# Steering_PCB.net
KiCad netlist of a schematic drawn in Altium Designer
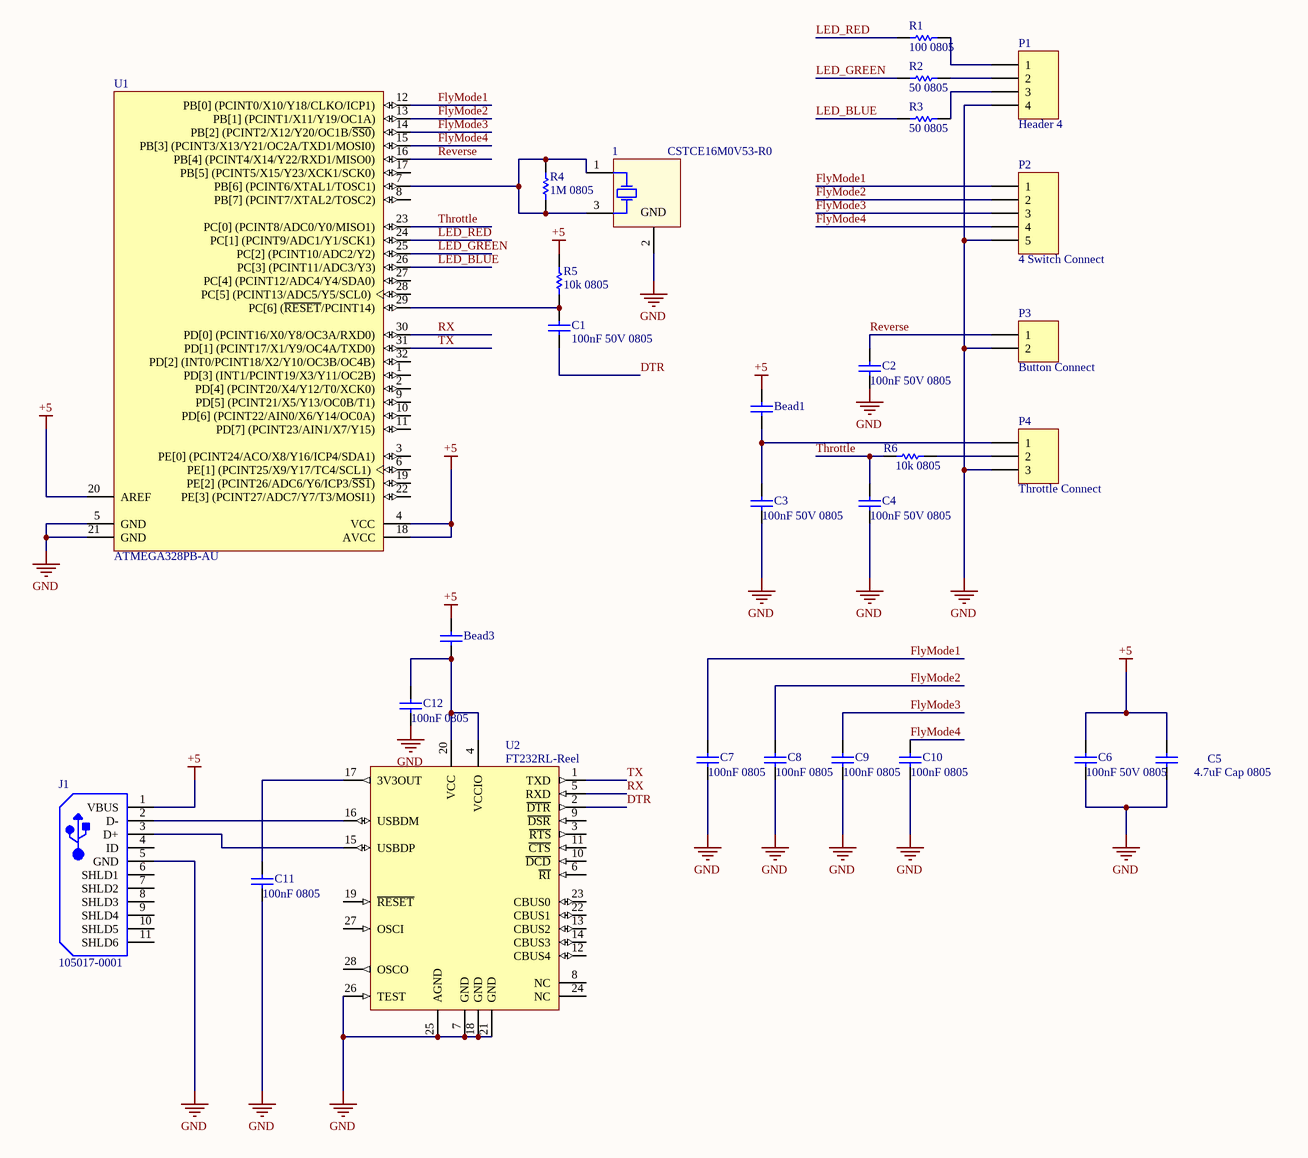
[diagram p0: Steering PCB.SchDoc]

(export (version "E")
  (design (tool "Eeschema 10.0.6"))
  (components
    (comp (ref "1")
      (value "CSTCE16M0V53-R0")
      (footprint "MURA-CSTCE_V-3_V")
      (fields (field (name "MANUFACTURER") "Murata"))
      (libsource (lib "Altium Content Vault") (part "MURA-CSTCE_V-3"))
    )
    (comp (ref "Bead1")
      (value "100nF 50V 0805")
      (footprint "0805C_L")
      (fields
        (field (name "MANUFACTURER") "Yageo")
        (field (name "MANUFACTURER PART NUMBER") "CC0805ZRY5V9BB104")
        (field (name "TOLERANCE") "-20%, +80%")
      )
      (libsource (lib "WCT") (part "Cap100nF_50V_0805"))
    )
    (comp (ref "Bead3")
      (value "100nF 50V 0805")
      (footprint "0805C_L")
      (fields
        (field (name "MANUFACTURER") "Yageo")
        (field (name "MANUFACTURER PART NUMBER") "CC0805ZRY5V9BB104")
        (field (name "TOLERANCE") "-20%, +80%")
      )
      (libsource (lib "WCT") (part "Cap100nF_50V_0805"))
    )
    (comp (ref "C1")
      (value "100nF 50V 0805")
      (footprint "0805C_L")
      (fields
        (field (name "MANUFACTURER") "Yageo")
        (field (name "MANUFACTURER PART NUMBER") "CC0805ZRY5V9BB104")
        (field (name "TOLERANCE") "-20%, +80%")
      )
      (libsource (lib "WCT") (part "Cap100nF_50V_0805"))
    )
    (comp (ref "C2")
      (value "100nF 50V 0805")
      (footprint "0805C_L")
      (fields
        (field (name "MANUFACTURER") "Yageo")
        (field (name "MANUFACTURER PART NUMBER") "CC0805ZRY5V9BB104")
        (field (name "TOLERANCE") "-20%, +80%")
      )
      (libsource (lib "WCT") (part "Cap100nF_50V_0805"))
    )
    (comp (ref "C3")
      (value "100nF 50V 0805")
      (footprint "0805C_L")
      (fields
        (field (name "MANUFACTURER") "Yageo")
        (field (name "MANUFACTURER PART NUMBER") "CC0805ZRY5V9BB104")
        (field (name "TOLERANCE") "-20%, +80%")
      )
      (libsource (lib "WCT") (part "Cap100nF_50V_0805"))
    )
    (comp (ref "C4")
      (value "100nF 50V 0805")
      (footprint "0805C_L")
      (fields
        (field (name "MANUFACTURER") "Yageo")
        (field (name "MANUFACTURER PART NUMBER") "CC0805ZRY5V9BB104")
        (field (name "TOLERANCE") "-20%, +80%")
      )
      (libsource (lib "WCT") (part "Cap100nF_50V_0805"))
    )
    (comp (ref "C5")
      (value "4.7uF Cap 0805")
      (footprint "0805C_L")
      (fields
        (field (name "MANUFACTURER") "Yageo")
        (field (name "MANUFACTURER PART NUMBER") "CC0805ZRY5V9BB104")
        (field (name "TOLERANCE") "-20%, +80%")
      )
      (libsource (lib "WCT") (part "Cap100nF_50V_0805"))
    )
    (comp (ref "C6")
      (value "100nF 50V 0805")
      (footprint "0805C_L")
      (fields
        (field (name "MANUFACTURER") "Yageo")
        (field (name "MANUFACTURER PART NUMBER") "CC0805ZRY5V9BB104")
        (field (name "TOLERANCE") "-20%, +80%")
      )
      (libsource (lib "WCT") (part "Cap100nF_50V_0805"))
    )
    (comp (ref "C7")
      (value "100nF 0805")
      (footprint "0805C_L")
      (fields
        (field (name "MANUFACTURER") "Yageo")
        (field (name "MANUFACTURER PART NUMBER") "CC0805ZRY5V9BB104")
        (field (name "TOLERANCE") "-20%, +80%")
      )
      (libsource (lib "WCT") (part "Cap100nF_50V_0805"))
    )
    (comp (ref "C8")
      (value "100nF 0805")
      (footprint "0805C_L")
      (fields
        (field (name "MANUFACTURER") "Yageo")
        (field (name "MANUFACTURER PART NUMBER") "CC0805ZRY5V9BB104")
        (field (name "TOLERANCE") "-20%, +80%")
      )
      (libsource (lib "WCT") (part "Cap100nF_50V_0805"))
    )
    (comp (ref "C9")
      (value "100nF 0805")
      (footprint "0805C_L")
      (fields
        (field (name "MANUFACTURER") "Yageo")
        (field (name "MANUFACTURER PART NUMBER") "CC0805ZRY5V9BB104")
        (field (name "TOLERANCE") "-20%, +80%")
      )
      (libsource (lib "WCT") (part "Cap100nF_50V_0805"))
    )
    (comp (ref "C10")
      (value "100nF 0805")
      (footprint "0805C_L")
      (fields
        (field (name "MANUFACTURER") "Yageo")
        (field (name "MANUFACTURER PART NUMBER") "CC0805ZRY5V9BB104")
        (field (name "TOLERANCE") "-20%, +80%")
      )
      (libsource (lib "WCT") (part "Cap100nF_50V_0805"))
    )
    (comp (ref "C11")
      (value "100nF 0805")
      (footprint "0805C_L")
      (fields
        (field (name "MANUFACTURER") "Yageo")
        (field (name "MANUFACTURER PART NUMBER") "CC0805ZRY5V9BB104")
        (field (name "TOLERANCE") "-20%, +80%")
      )
      (libsource (lib "WCT") (part "Cap100nF_50V_0805"))
    )
    (comp (ref "C12")
      (value "100nF 0805")
      (footprint "0805C_L")
      (fields
        (field (name "MANUFACTURER") "Yageo")
        (field (name "MANUFACTURER PART NUMBER") "CC0805ZRY5V9BB104")
        (field (name "TOLERANCE") "-20%, +80%")
      )
      (libsource (lib "WCT") (part "Cap100nF_50V_0805"))
    )
    (comp (ref "J1")
      (value "105017-0001")
      (footprint "USB-MICRO-B_V")
      (fields (field (name "MANUFACTURER") "Molex"))
      (libsource (lib "Altium Content Vault") (part "USB-5-6SHLD"))
    )
    (comp (ref "P1")
      (value "Header 4")
      (footprint "HDR1X4")
      (description "Header, 4-Pin")
      (fields (field (name "PUBLISHER") "Altium Limited"))
      (libsource (lib "Miscellaneous Connectors") (part "Header 4"))
    )
    (comp (ref "P2")
      (value "4 Switch Connect")
      (footprint "HDR1X5")
      (description "Header, 5-Pin")
      (fields (field (name "PUBLISHER") "Altium Limited"))
      (libsource (lib "Miscellaneous Connectors") (part "Header 5"))
    )
    (comp (ref "P3")
      (value "Button Connect")
      (footprint "HDR1X2")
      (description "Header, 2-Pin")
      (fields (field (name "PUBLISHER") "Altium Limited"))
      (libsource (lib "Miscellaneous Connectors") (part "Header 2"))
    )
    (comp (ref "P4")
      (value "Throttle Connect")
      (footprint "HDR1X3")
      (description "Header, 3-Pin")
      (fields (field (name "PUBLISHER") "Altium Limited"))
      (libsource (lib "Miscellaneous Connectors") (part "Header 3"))
    )
    (comp (ref "R1")
      (value "100 0805")
      (footprint "RESC0805(2012)_M")
      (description "39R2 0.125W 1% 0805 (2012 Metric)  SMD")
      (fields (field (name "TOLERANCE") "1 %") (field (name "POWER") "0.125 W"))
      (libsource (lib "Altium Content Vault") (part "RES"))
    )
    (comp (ref "R2")
      (value "50 0805")
      (footprint "RESC0805(2012)_M")
      (description "39R2 0.125W 1% 0805 (2012 Metric)  SMD")
      (fields (field (name "TOLERANCE") "1 %") (field (name "POWER") "0.125 W"))
      (libsource (lib "Altium Content Vault") (part "RES"))
    )
    (comp (ref "R3")
      (value "50 0805")
      (footprint "RESC0805(2012)_M")
      (description "39R2 0.125W 1% 0805 (2012 Metric)  SMD")
      (fields (field (name "TOLERANCE") "1 %") (field (name "POWER") "0.125 W"))
      (libsource (lib "Altium Content Vault") (part "RES"))
    )
    (comp (ref "R4")
      (value "1M 0805")
      (footprint "RESC0805(2012)_M")
      (description "39R2 0.125W 1% 0805 (2012 Metric)  SMD")
      (fields (field (name "TOLERANCE") "1 %") (field (name "POWER") "0.125 W"))
      (libsource (lib "Altium Content Vault") (part "RES"))
    )
    (comp (ref "R5")
      (value "10k 0805")
      (footprint "RESC0805(2012)_M")
      (description "39R2 0.125W 1% 0805 (2012 Metric)  SMD")
      (fields (field (name "TOLERANCE") "1 %") (field (name "POWER") "0.125 W"))
      (libsource (lib "Altium Content Vault") (part "RES"))
    )
    (comp (ref "R6")
      (value "10k 0805")
      (footprint "RESC0805(2012)_M")
      (description "39R2 0.125W 1% 0805 (2012 Metric)  SMD")
      (fields (field (name "TOLERANCE") "1 %") (field (name "POWER") "0.125 W"))
      (libsource (lib "Altium Content Vault") (part "RES"))
    )
    (comp (ref "U1")
      (value "ATMEGA328PB-AU")
      (footprint "ATML-32A_L")
      (fields (field (name "MANUFACTURER") "Microchip"))
      (libsource (lib "Altium Content Vault") (part "ATML-ATMEGA328PB-32A"))
    )
    (comp (ref "U2")
      (value "FT232RL-Reel")
      (footprint "SSOP-28_N")
      (description "USB UART Asynchronous Serial Data Transfer Chip, SSOP-28, Tape and Reel")
      (libsource (lib "Altium Content Vault") (part "COM-UART-FT232R-IL28"))
    )
  )
  (nets
    (net (code "1") (name "+5") (class "Default")
      (node (ref "Bead1") (pin "2") (pinfunction "2_2") (pintype "passive"))
      (node (ref "Bead3") (pin "2") (pinfunction "2_2") (pintype "passive"))
      (node (ref "C5") (pin "2") (pinfunction "2_2") (pintype "passive"))
      (node (ref "C6") (pin "2") (pinfunction "2_2") (pintype "passive"))
      (node (ref "J1") (pin "1") (pinfunction "VBUS_1") (pintype "passive"))
      (node (ref "R5") (pin "2") (pinfunction "2_2") (pintype "passive"))
      (node (ref "U1") (pin "18") (pinfunction "AVCC_18") (pintype "power_in"))
      (node (ref "U1") (pin "20") (pinfunction "AREF_20") (pintype "passive"))
      (node (ref "U1") (pin "4") (pinfunction "VCC_4") (pintype "power_in"))
    )
    (net (code "2") (name "/DTR") (class "Default")
      (node (ref "C1") (pin "1") (pinfunction "1_1") (pintype "passive"))
      (node (ref "U2") (pin "2") (pinfunction "~{DTR}_2") (pintype "output"))
    )
    (net (code "3") (name "/FlyMode1") (class "Default")
      (node (ref "C7") (pin "2") (pinfunction "2_2") (pintype "passive"))
      (node (ref "P2") (pin "1") (pinfunction "1_1") (pintype "passive"))
      (node (ref "U1") (pin "12") (pinfunction "PB[0]_(PCINT0/X10/Y18/CLKO/ICP1)_12") (pintype "bidirectional"))
    )
    (net (code "4") (name "/FlyMode2") (class "Default")
      (node (ref "C8") (pin "2") (pinfunction "2_2") (pintype "passive"))
      (node (ref "P2") (pin "2") (pinfunction "2_2") (pintype "passive"))
      (node (ref "U1") (pin "13") (pinfunction "PB[1]_(PCINT1/X11/Y19/OC1A)_13") (pintype "bidirectional"))
    )
    (net (code "5") (name "/FlyMode3") (class "Default")
      (node (ref "C9") (pin "2") (pinfunction "2_2") (pintype "passive"))
      (node (ref "P2") (pin "3") (pinfunction "3_3") (pintype "passive"))
      (node (ref "U1") (pin "14") (pinfunction "PB[2]_(PCINT2/X12/Y20/OC1B/~{SS0})_14") (pintype "bidirectional"))
    )
    (net (code "6") (name "/FlyMode4") (class "Default")
      (node (ref "C10") (pin "2") (pinfunction "2_2") (pintype "passive"))
      (node (ref "P2") (pin "4") (pinfunction "4_4") (pintype "passive"))
      (node (ref "U1") (pin "15") (pinfunction "PB[3]_(PCINT3/X13/Y21/OC2A/TXD1/MOSI0)_15") (pintype "bidirectional"))
    )
    (net (code "7") (name "/LED_BLUE") (class "Default")
      (node (ref "R3") (pin "2") (pinfunction "2_2") (pintype "passive"))
      (node (ref "U1") (pin "26") (pinfunction "PC[3]_(PCINT11/ADC3/Y3)_26") (pintype "bidirectional"))
    )
    (net (code "8") (name "/LED_GREEN") (class "Default")
      (node (ref "R2") (pin "2") (pinfunction "2_2") (pintype "passive"))
      (node (ref "U1") (pin "25") (pinfunction "PC[2]_(PCINT10/ADC2/Y2)_25") (pintype "bidirectional"))
    )
    (net (code "9") (name "/LED_RED") (class "Default")
      (node (ref "R1") (pin "2") (pinfunction "2_2") (pintype "passive"))
      (node (ref "U1") (pin "24") (pinfunction "PC[1]_(PCINT9/ADC1/Y1/SCK1)_24") (pintype "bidirectional"))
    )
    (net (code "10") (name "/RX") (class "Default")
      (node (ref "U1") (pin "30") (pinfunction "PD[0]_(PCINT16/X0/Y8/OC3A/RXD0)_30") (pintype "bidirectional"))
      (node (ref "U2") (pin "5") (pinfunction "RXD_5") (pintype "input"))
    )
    (net (code "11") (name "/Reverse") (class "Default")
      (node (ref "C2") (pin "2") (pinfunction "2_2") (pintype "passive"))
      (node (ref "P3") (pin "1") (pinfunction "1_1") (pintype "passive"))
      (node (ref "U1") (pin "16") (pinfunction "PB[4]_(PCINT4/X14/Y22/RXD1/MISO0)_16") (pintype "bidirectional"))
    )
    (net (code "12") (name "/TX") (class "Default")
      (node (ref "U1") (pin "31") (pinfunction "PD[1]_(PCINT17/X1/Y9/OC4A/TXD0)_31") (pintype "bidirectional"))
      (node (ref "U2") (pin "1") (pinfunction "TXD_1") (pintype "output"))
    )
    (net (code "13") (name "/Throttle") (class "Default")
      (node (ref "C4") (pin "2") (pinfunction "2_2") (pintype "passive"))
      (node (ref "R6") (pin "2") (pinfunction "2_2") (pintype "passive"))
      (node (ref "U1") (pin "23") (pinfunction "PC[0]_(PCINT8/ADC0/Y0/MISO1)_23") (pintype "bidirectional"))
    )
    (net (code "14") (name "GND") (class "Default")
      (node (ref "1") (pin "2") (pinfunction "GND_2") (pintype "power_in"))
      (node (ref "C10") (pin "1") (pinfunction "1_1") (pintype "passive"))
      (node (ref "C11") (pin "1") (pinfunction "1_1") (pintype "passive"))
      (node (ref "C12") (pin "1") (pinfunction "1_1") (pintype "passive"))
      (node (ref "C2") (pin "1") (pinfunction "1_1") (pintype "passive"))
      (node (ref "C3") (pin "1") (pinfunction "1_1") (pintype "passive"))
      (node (ref "C4") (pin "1") (pinfunction "1_1") (pintype "passive"))
      (node (ref "C5") (pin "1") (pinfunction "1_1") (pintype "passive"))
      (node (ref "C6") (pin "1") (pinfunction "1_1") (pintype "passive"))
      (node (ref "C7") (pin "1") (pinfunction "1_1") (pintype "passive"))
      (node (ref "C8") (pin "1") (pinfunction "1_1") (pintype "passive"))
      (node (ref "C9") (pin "1") (pinfunction "1_1") (pintype "passive"))
      (node (ref "J1") (pin "5") (pinfunction "GND_5") (pintype "passive"))
      (node (ref "P1") (pin "4") (pinfunction "4_4") (pintype "passive"))
      (node (ref "P2") (pin "5") (pinfunction "5_5") (pintype "passive"))
      (node (ref "P3") (pin "2") (pinfunction "2_2") (pintype "passive"))
      (node (ref "P4") (pin "3") (pinfunction "3_3") (pintype "passive"))
      (node (ref "U1") (pin "21") (pinfunction "GND_21") (pintype "power_in"))
      (node (ref "U1") (pin "5") (pinfunction "GND_5") (pintype "power_in"))
      (node (ref "U2") (pin "18") (pinfunction "GND_18") (pintype "power_in"))
      (node (ref "U2") (pin "21") (pinfunction "GND_21") (pintype "power_in"))
      (node (ref "U2") (pin "25") (pinfunction "AGND_25") (pintype "power_in"))
      (node (ref "U2") (pin "26") (pinfunction "TEST_26") (pintype "input"))
      (node (ref "U2") (pin "7") (pinfunction "GND_7") (pintype "power_in"))
    )
    (net (code "15") (name "Net-(1-C1)") (class "Default")
      (node (ref "1") (pin "1") (pinfunction "C1_1") (pintype "passive"))
      (node (ref "1") (pin "3") (pinfunction "C2_3") (pintype "passive"))
      (node (ref "R4") (pin "1") (pinfunction "1_1") (pintype "passive"))
      (node (ref "R4") (pin "2") (pinfunction "2_2") (pintype "passive"))
      (node (ref "U1") (pin "7") (pinfunction "PB[6]_(PCINT6/XTAL1/TOSC1)_7") (pintype "bidirectional"))
    )
    (net (code "16") (name "Net-(Bead1-Pad1)") (class "Default")
      (node (ref "Bead1") (pin "1") (pinfunction "1_1") (pintype "passive"))
      (node (ref "C3") (pin "2") (pinfunction "2_2") (pintype "passive"))
      (node (ref "P4") (pin "1") (pinfunction "1_1") (pintype "passive"))
    )
    (net (code "17") (name "Net-(J1-D+)") (class "Default")
      (node (ref "J1") (pin "3") (pinfunction "D+_3") (pintype "passive"))
      (node (ref "U2") (pin "15") (pinfunction "USBDP_15") (pintype "bidirectional"))
    )
    (net (code "18") (name "Net-(J1-D-)") (class "Default")
      (node (ref "J1") (pin "2") (pinfunction "D-_2") (pintype "passive"))
      (node (ref "U2") (pin "16") (pinfunction "USBDM_16") (pintype "bidirectional"))
    )
    (net (code "19") (name "Net-(P1-Pad1)") (class "Default")
      (node (ref "P1") (pin "1") (pinfunction "1_1") (pintype "passive"))
      (node (ref "R1") (pin "1") (pinfunction "1_1") (pintype "passive"))
    )
    (net (code "20") (name "Net-(P1-Pad2)") (class "Default")
      (node (ref "P1") (pin "2") (pinfunction "2_2") (pintype "passive"))
      (node (ref "R2") (pin "1") (pinfunction "1_1") (pintype "passive"))
    )
    (net (code "21") (name "Net-(P1-Pad3)") (class "Default")
      (node (ref "P1") (pin "3") (pinfunction "3_3") (pintype "passive"))
      (node (ref "R3") (pin "1") (pinfunction "1_1") (pintype "passive"))
    )
    (net (code "22") (name "Net-(P4-Pad2)") (class "Default")
      (node (ref "P4") (pin "2") (pinfunction "2_2") (pintype "passive"))
      (node (ref "R6") (pin "1") (pinfunction "1_1") (pintype "passive"))
    )
    (net (code "23") (name "Net-(U1-PC[6]_(~{RESET}{slash}PCINT14))") (class "Default")
      (node (ref "C1") (pin "2") (pinfunction "2_2") (pintype "passive"))
      (node (ref "R5") (pin "1") (pinfunction "1_1") (pintype "passive"))
      (node (ref "U1") (pin "29") (pinfunction "PC[6]_(~{RESET}/PCINT14)_29") (pintype "bidirectional"))
    )
    (net (code "24") (name "Net-(U2-3V3OUT)") (class "Default")
      (node (ref "C11") (pin "2") (pinfunction "2_2") (pintype "passive"))
      (node (ref "U2") (pin "17") (pinfunction "3V3OUT_17") (pintype "output"))
    )
    (net (code "25") (name "Net-(U2-VCC)") (class "Default")
      (node (ref "Bead3") (pin "1") (pinfunction "1_1") (pintype "passive"))
      (node (ref "C12") (pin "2") (pinfunction "2_2") (pintype "passive"))
      (node (ref "U2") (pin "20") (pinfunction "VCC_20") (pintype "power_in"))
      (node (ref "U2") (pin "4") (pinfunction "VCCIO_4") (pintype "power_in"))
    )
    (net (code "26") (name "unconnected-(J1-ID-Pad4)") (class "Default")
      (node (ref "J1") (pin "4") (pinfunction "ID_4") (pintype "passive"))
    )
    (net (code "27") (name "unconnected-(J1-SHLD1-Pad6)") (class "Default")
      (node (ref "J1") (pin "6") (pinfunction "SHLD1_6") (pintype "passive"))
    )
    (net (code "28") (name "unconnected-(J1-SHLD2-Pad7)") (class "Default")
      (node (ref "J1") (pin "7") (pinfunction "SHLD2_7") (pintype "passive"))
    )
    (net (code "29") (name "unconnected-(J1-SHLD3-Pad8)") (class "Default")
      (node (ref "J1") (pin "8") (pinfunction "SHLD3_8") (pintype "passive"))
    )
    (net (code "30") (name "unconnected-(J1-SHLD4-Pad9)") (class "Default")
      (node (ref "J1") (pin "9") (pinfunction "SHLD4_9") (pintype "passive"))
    )
    (net (code "31") (name "unconnected-(J1-SHLD5-Pad10)") (class "Default")
      (node (ref "J1") (pin "10") (pinfunction "SHLD5_10") (pintype "passive"))
    )
    (net (code "32") (name "unconnected-(J1-SHLD6-Pad11)") (class "Default")
      (node (ref "J1") (pin "11") (pinfunction "SHLD6_11") (pintype "passive"))
    )
    (net (code "33") (name "unconnected-(U1-PB[5]_(PCINT5{slash}X15{slash}Y23{slash}XCK1{slash}SCK0)-Pad17)") (class "Default")
      (node (ref "U1") (pin "17") (pinfunction "PB[5]_(PCINT5/X15/Y23/XCK1/SCK0)_17") (pintype "bidirectional"))
    )
    (net (code "34") (name "unconnected-(U1-PB[7]_(PCINT7{slash}XTAL2{slash}TOSC2)-Pad8)") (class "Default")
      (node (ref "U1") (pin "8") (pinfunction "PB[7]_(PCINT7/XTAL2/TOSC2)_8") (pintype "bidirectional"))
    )
    (net (code "35") (name "unconnected-(U1-PC[4]_(PCINT12{slash}ADC4{slash}Y4{slash}SDA0)-Pad27)") (class "Default")
      (node (ref "U1") (pin "27") (pinfunction "PC[4]_(PCINT12/ADC4/Y4/SDA0)_27") (pintype "bidirectional"))
    )
    (net (code "36") (name "unconnected-(U1-PC[5]_(PCINT13{slash}ADC5{slash}Y5{slash}SCL0)-Pad28)") (class "Default")
      (node (ref "U1") (pin "28") (pinfunction "PC[5]_(PCINT13/ADC5/Y5/SCL0)_28") (pintype "bidirectional"))
    )
    (net (code "37") (name "unconnected-(U1-PD[2]_(INT0{slash}PCINT18{slash}X2{slash}Y10{slash}OC3B{slash}OC4B)-Pad32)") (class "Default")
      (node (ref "U1") (pin "32") (pinfunction "PD[2]_(INT0/PCINT18/X2/Y10/OC3B/OC4B)_32") (pintype "bidirectional"))
    )
    (net (code "38") (name "unconnected-(U1-PD[3]_(INT1{slash}PCINT19{slash}X3{slash}Y11{slash}OC2B)-Pad1)") (class "Default")
      (node (ref "U1") (pin "1") (pinfunction "PD[3]_(INT1/PCINT19/X3/Y11/OC2B)_1") (pintype "bidirectional"))
    )
    (net (code "39") (name "unconnected-(U1-PD[4]_(PCINT20{slash}X4{slash}Y12{slash}T0{slash}XCK0)-Pad2)") (class "Default")
      (node (ref "U1") (pin "2") (pinfunction "PD[4]_(PCINT20/X4/Y12/T0/XCK0)_2") (pintype "bidirectional"))
    )
    (net (code "40") (name "unconnected-(U1-PD[5]_(PCINT21{slash}X5{slash}Y13{slash}OC0B{slash}T1)-Pad9)") (class "Default")
      (node (ref "U1") (pin "9") (pinfunction "PD[5]_(PCINT21/X5/Y13/OC0B/T1)_9") (pintype "bidirectional"))
    )
    (net (code "41") (name "unconnected-(U1-PD[6]_(PCINT22{slash}AIN0{slash}X6{slash}Y14{slash}OC0A)-Pad10)") (class "Default")
      (node (ref "U1") (pin "10") (pinfunction "PD[6]_(PCINT22/AIN0/X6/Y14/OC0A)_10") (pintype "bidirectional"))
    )
    (net (code "42") (name "unconnected-(U1-PD[7]_(PCINT23{slash}AIN1{slash}X7{slash}Y15)-Pad11)") (class "Default")
      (node (ref "U1") (pin "11") (pinfunction "PD[7]_(PCINT23/AIN1/X7/Y15)_11") (pintype "bidirectional"))
    )
    (net (code "43") (name "unconnected-(U1-PE[0]_(PCINT24{slash}ACO{slash}X8{slash}Y16{slash}ICP4{slash}SDA1)-Pad3)") (class "Default")
      (node (ref "U1") (pin "3") (pinfunction "PE[0]_(PCINT24/ACO/X8/Y16/ICP4/SDA1)_3") (pintype "bidirectional"))
    )
    (net (code "44") (name "unconnected-(U1-PE[1]_(PCINT25{slash}X9{slash}Y17{slash}TC4{slash}SCL1)-Pad6)") (class "Default")
      (node (ref "U1") (pin "6") (pinfunction "PE[1]_(PCINT25/X9/Y17/TC4/SCL1)_6") (pintype "bidirectional"))
    )
    (net (code "45") (name "unconnected-(U1-PE[2]_(PCINT26{slash}ADC6{slash}Y6{slash}ICP3{slash}~{SS1})-Pad19)") (class "Default")
      (node (ref "U1") (pin "19") (pinfunction "PE[2]_(PCINT26/ADC6/Y6/ICP3/~{SS1})_19") (pintype "bidirectional"))
    )
    (net (code "46") (name "unconnected-(U1-PE[3]_(PCINT27{slash}ADC7{slash}Y7{slash}T3{slash}MOSI1)-Pad22)") (class "Default")
      (node (ref "U1") (pin "22") (pinfunction "PE[3]_(PCINT27/ADC7/Y7/T3/MOSI1)_22") (pintype "bidirectional"))
    )
    (net (code "47") (name "unconnected-(U2-CBUS0-Pad23)") (class "Default")
      (node (ref "U2") (pin "23") (pinfunction "CBUS0_23") (pintype "bidirectional"))
    )
    (net (code "48") (name "unconnected-(U2-CBUS1-Pad22)") (class "Default")
      (node (ref "U2") (pin "22") (pinfunction "CBUS1_22") (pintype "bidirectional"))
    )
    (net (code "49") (name "unconnected-(U2-CBUS2-Pad13)") (class "Default")
      (node (ref "U2") (pin "13") (pinfunction "CBUS2_13") (pintype "bidirectional"))
    )
    (net (code "50") (name "unconnected-(U2-CBUS3-Pad14)") (class "Default")
      (node (ref "U2") (pin "14") (pinfunction "CBUS3_14") (pintype "bidirectional"))
    )
    (net (code "51") (name "unconnected-(U2-CBUS4-Pad12)") (class "Default")
      (node (ref "U2") (pin "12") (pinfunction "CBUS4_12") (pintype "bidirectional"))
    )
    (net (code "52") (name "unconnected-(U2-NC-Pad8)") (class "Default")
      (node (ref "U2") (pin "8") (pinfunction "NC_8") (pintype "passive"))
    )
    (net (code "53") (name "unconnected-(U2-NC-Pad24)") (class "Default")
      (node (ref "U2") (pin "24") (pinfunction "NC_24") (pintype "passive"))
    )
    (net (code "54") (name "unconnected-(U2-OSCI-Pad27)") (class "Default")
      (node (ref "U2") (pin "27") (pinfunction "OSCI_27") (pintype "input"))
    )
    (net (code "55") (name "unconnected-(U2-OSCO-Pad28)") (class "Default")
      (node (ref "U2") (pin "28") (pinfunction "OSCO_28") (pintype "output"))
    )
    (net (code "56") (name "unconnected-(U2-~{CTS}-Pad11)") (class "Default")
      (node (ref "U2") (pin "11") (pinfunction "~{CTS}_11") (pintype "input"))
    )
    (net (code "57") (name "unconnected-(U2-~{DCD}-Pad10)") (class "Default")
      (node (ref "U2") (pin "10") (pinfunction "~{DCD}_10") (pintype "input"))
    )
    (net (code "58") (name "unconnected-(U2-~{DSR}-Pad9)") (class "Default")
      (node (ref "U2") (pin "9") (pinfunction "~{DSR}_9") (pintype "input"))
    )
    (net (code "59") (name "unconnected-(U2-~{RESET}-Pad19)") (class "Default")
      (node (ref "U2") (pin "19") (pinfunction "~{RESET}_19") (pintype "input"))
    )
    (net (code "60") (name "unconnected-(U2-~{RI}-Pad6)") (class "Default")
      (node (ref "U2") (pin "6") (pinfunction "~{RI}_6") (pintype "input"))
    )
    (net (code "61") (name "unconnected-(U2-~{RTS}-Pad3)") (class "Default")
      (node (ref "U2") (pin "3") (pinfunction "~{RTS}_3") (pintype "output"))
    )
  )
)
